# CONN_BOTT.net
KiCad netlist of a schematic drawn in Altium Designer
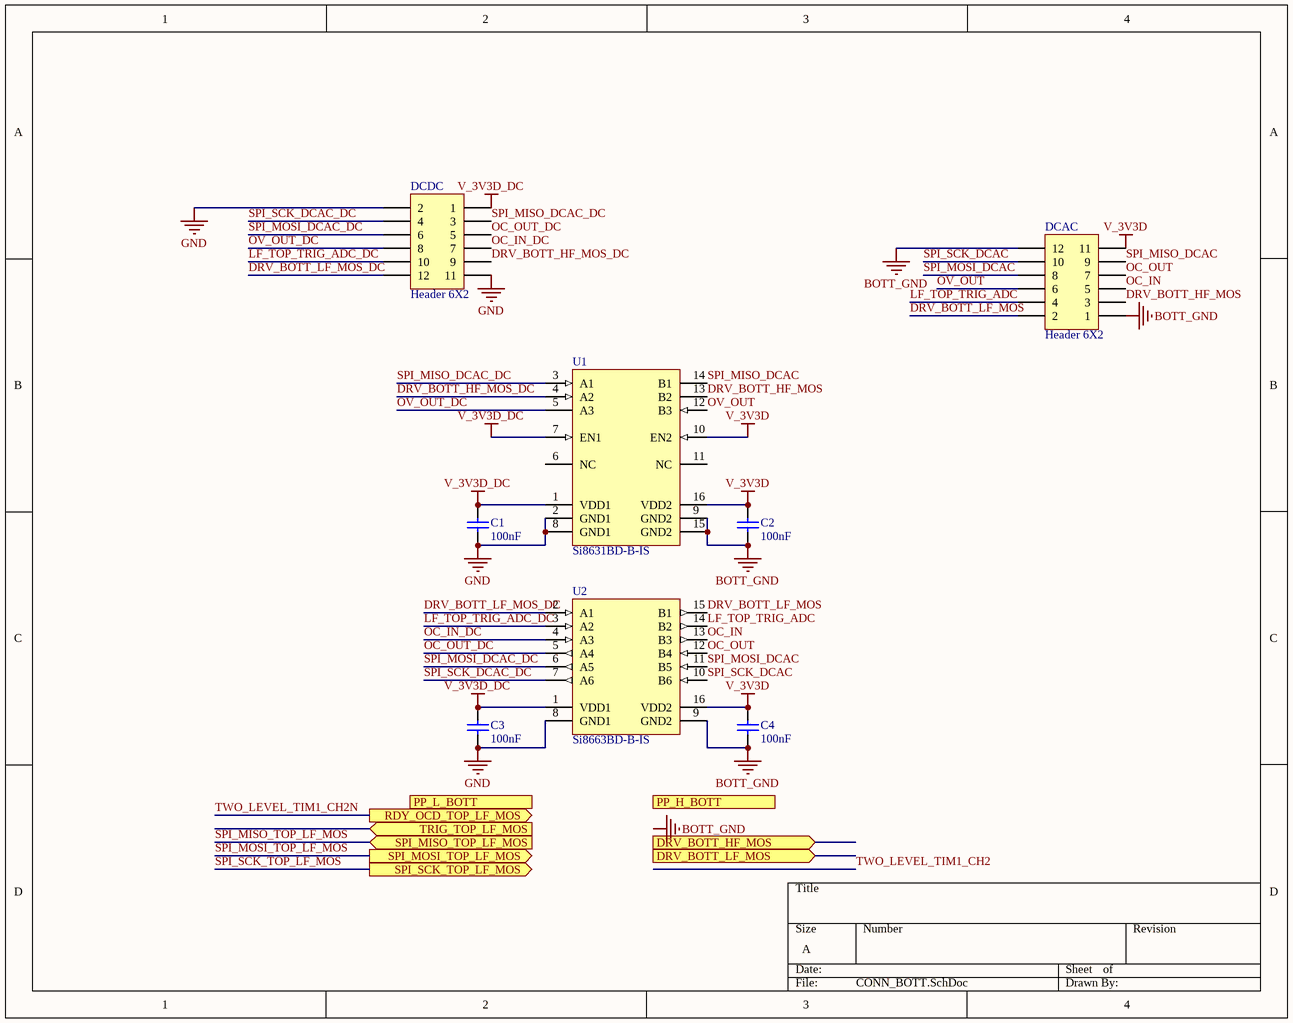
[diagram p0: CONN_BOTT.SchDoc]

(export (version "E")
  (design (tool "Eeschema 10.0.6"))
  (components
    (comp (ref "C1")
      (value "100nF")
      (footprint "SAMS-C0603-2_N")
      (description "Cap Ceramic 0.1uF 50VDC X7R 10% SMD 0603 Paper T/R")
      (fields
        (field (name "MANUFACTURER") "Samsung Electro-Mechanics")
        (field (name "MANUFACTURER PART NUMBER") "CL10B104KB8NNNC")
      )
      (libsource (lib "Altium Content Vault") (part "CAP-NP-2"))
    )
    (comp (ref "C2")
      (value "100nF")
      (footprint "SAMS-C0603-2_N")
      (description "Cap Ceramic 0.1uF 50VDC X7R 10% SMD 0603 Paper T/R")
      (fields
        (field (name "MANUFACTURER") "Samsung Electro-Mechanics")
        (field (name "MANUFACTURER PART NUMBER") "CL10B104KB8NNNC")
      )
      (libsource (lib "Altium Content Vault") (part "CAP-NP-2"))
    )
    (comp (ref "C3")
      (value "100nF")
      (footprint "SAMS-C0603-2_N")
      (description "Cap Ceramic 0.1uF 50VDC X7R 10% SMD 0603 Paper T/R")
      (fields
        (field (name "MANUFACTURER") "Samsung Electro-Mechanics")
        (field (name "MANUFACTURER PART NUMBER") "CL10B104KB8NNNC")
      )
      (libsource (lib "Altium Content Vault") (part "CAP-NP-2"))
    )
    (comp (ref "C4")
      (value "100nF")
      (footprint "SAMS-C0603-2_N")
      (description "Cap Ceramic 0.1uF 50VDC X7R 10% SMD 0603 Paper T/R")
      (fields
        (field (name "MANUFACTURER") "Samsung Electro-Mechanics")
        (field (name "MANUFACTURER PART NUMBER") "CL10B104KB8NNNC")
      )
      (libsource (lib "Altium Content Vault") (part "CAP-NP-2"))
    )
    (comp (ref "DCAC")
      (value "Header 6X2")
      (footprint "EDGE GOLDPIN 12P 1.27mm")
      (description "Header, 6-Pin, Dual row")
      (fields (field (name "PUBLISHER") "Altium Limited"))
      (libsource (lib "Miscellaneous Connectors") (part "Header 6X2"))
    )
    (comp (ref "DCDC")
      (value "Header 6X2")
      (footprint "EDGE GOLDPIN 12P 1.27mm")
      (description "Header, 6-Pin, Dual row")
      (fields (field (name "PUBLISHER") "Altium Limited"))
      (libsource (lib "") (part "Header 6X2_1"))
    )
    (comp (ref "U1")
      (value "Si8631BD-B-IS")
      (footprint "SLAB-SOIC-16-WB_N")
      (fields (field (name "MANUFACTURER") "Silicon Labs"))
      (libsource (lib "Altium Content Vault") (part "SLAB-Si8X31BB-SOIC-16-XB-16X"))
    )
    (comp (ref "U2")
      (value "Si8663BD-B-IS")
      (footprint "SLAB-SOIC-16-WB_N")
      (fields (field (name "MANUFACTURER") "Silicon Labs"))
      (libsource (lib "Altium Content Vault") (part "SLAB-Si8X63-SOIC-16"))
    )
  )
  (nets
    (net (code "1") (name "/DRV_BOTT_HF_MOS") (class "Default")
      (node (ref "DCAC") (pin "3") (pinfunction "3_3") (pintype "passive"))
      (node (ref "U1") (pin "13") (pinfunction "B2_13") (pintype "tri_state"))
    )
    (net (code "2") (name "/DRV_BOTT_HF_MOS_DC") (class "Default")
      (node (ref "DCDC") (pin "9") (pinfunction "9_9") (pintype "passive"))
      (node (ref "U1") (pin "4") (pinfunction "A2_4") (pintype "input"))
    )
    (net (code "3") (name "/DRV_BOTT_LF_MOS") (class "Default")
      (node (ref "DCAC") (pin "2") (pinfunction "2_2") (pintype "passive"))
      (node (ref "U2") (pin "15") (pinfunction "B1_15") (pintype "output"))
    )
    (net (code "4") (name "/DRV_BOTT_LF_MOS_DC") (class "Default")
      (node (ref "DCDC") (pin "12") (pinfunction "12_12") (pintype "passive"))
      (node (ref "U2") (pin "2") (pinfunction "A1_2") (pintype "input"))
    )
    (net (code "5") (name "/LF_TOP_TRIG_ADC") (class "Default")
      (node (ref "DCAC") (pin "4") (pinfunction "4_4") (pintype "passive"))
      (node (ref "U2") (pin "14") (pinfunction "B2_14") (pintype "output"))
    )
    (net (code "6") (name "/LF_TOP_TRIG_ADC_DC") (class "Default")
      (node (ref "DCDC") (pin "10") (pinfunction "10_10") (pintype "passive"))
      (node (ref "U2") (pin "3") (pinfunction "A2_3") (pintype "input"))
    )
    (net (code "7") (name "/OC_IN") (class "Default")
      (node (ref "DCAC") (pin "5") (pinfunction "5_5") (pintype "passive"))
      (node (ref "U2") (pin "13") (pinfunction "B3_13") (pintype "output"))
    )
    (net (code "8") (name "/OC_IN_DC") (class "Default")
      (node (ref "DCDC") (pin "7") (pinfunction "7_7") (pintype "passive"))
      (node (ref "U2") (pin "4") (pinfunction "A3_4") (pintype "input"))
    )
    (net (code "9") (name "/OC_OUT") (class "Default")
      (node (ref "DCAC") (pin "7") (pinfunction "7_7") (pintype "passive"))
      (node (ref "U2") (pin "12") (pinfunction "B4_12") (pintype "input"))
    )
    (net (code "10") (name "/OC_OUT_DC") (class "Default")
      (node (ref "DCDC") (pin "5") (pinfunction "5_5") (pintype "passive"))
      (node (ref "U2") (pin "5") (pinfunction "A4_5") (pintype "output"))
    )
    (net (code "11") (name "/OV_OUT") (class "Default")
      (node (ref "DCAC") (pin "6") (pinfunction "6_6") (pintype "passive"))
      (node (ref "U1") (pin "12") (pinfunction "B3_12") (pintype "input"))
    )
    (net (code "12") (name "/OV_OUT_DC") (class "Default")
      (node (ref "DCDC") (pin "8") (pinfunction "8_8") (pintype "passive"))
      (node (ref "U1") (pin "5") (pinfunction "A3_5") (pintype "tri_state"))
    )
    (net (code "15") (name "/SPI_MISO_DCAC") (class "Default")
      (node (ref "DCAC") (pin "9") (pinfunction "9_9") (pintype "passive"))
      (node (ref "U1") (pin "14") (pinfunction "B1_14") (pintype "tri_state"))
    )
    (net (code "16") (name "/SPI_MISO_DCAC_DC") (class "Default")
      (node (ref "DCDC") (pin "3") (pinfunction "3_3") (pintype "passive"))
      (node (ref "U1") (pin "3") (pinfunction "A1_3") (pintype "input"))
    )
    (net (code "18") (name "/SPI_MOSI_DCAC") (class "Default")
      (node (ref "DCAC") (pin "8") (pinfunction "8_8") (pintype "passive"))
      (node (ref "U2") (pin "11") (pinfunction "B5_11") (pintype "input"))
    )
    (net (code "19") (name "/SPI_MOSI_DCAC_DC") (class "Default")
      (node (ref "DCDC") (pin "6") (pinfunction "6_6") (pintype "passive"))
      (node (ref "U2") (pin "6") (pinfunction "A5_6") (pintype "output"))
    )
    (net (code "21") (name "/SPI_SCK_DCAC") (class "Default")
      (node (ref "DCAC") (pin "10") (pinfunction "10_10") (pintype "passive"))
      (node (ref "U2") (pin "10") (pinfunction "B6_10") (pintype "input"))
    )
    (net (code "22") (name "/SPI_SCK_DCAC_DC") (class "Default")
      (node (ref "DCDC") (pin "4") (pinfunction "4_4") (pintype "passive"))
      (node (ref "U2") (pin "7") (pinfunction "A6_7") (pintype "output"))
    )
    (net (code "27") (name "BOTT_GND") (class "Default")
      (node (ref "C2") (pin "2") (pinfunction "2_2") (pintype "passive"))
      (node (ref "C4") (pin "2") (pinfunction "2_2") (pintype "passive"))
      (node (ref "DCAC") (pin "1") (pinfunction "1_1") (pintype "passive"))
      (node (ref "DCAC") (pin "12") (pinfunction "12_12") (pintype "passive"))
      (node (ref "U1") (pin "15") (pinfunction "GND2_15") (pintype "power_in"))
      (node (ref "U1") (pin "9") (pinfunction "GND2_9") (pintype "power_in"))
      (node (ref "U2") (pin "9") (pinfunction "GND2_9") (pintype "power_in"))
    )
    (net (code "28") (name "GND") (class "Default")
      (node (ref "C1") (pin "2") (pinfunction "2_2") (pintype "passive"))
      (node (ref "C3") (pin "2") (pinfunction "2_2") (pintype "passive"))
      (node (ref "DCDC") (pin "11") (pinfunction "11_11") (pintype "passive"))
      (node (ref "DCDC") (pin "2") (pinfunction "2_2") (pintype "passive"))
      (node (ref "U1") (pin "2") (pinfunction "GND1_2") (pintype "power_in"))
      (node (ref "U1") (pin "8") (pinfunction "GND1_8") (pintype "power_in"))
      (node (ref "U2") (pin "8") (pinfunction "GND1_8") (pintype "power_in"))
    )
    (net (code "29") (name "V_3V3D") (class "Default")
      (node (ref "C2") (pin "1") (pinfunction "1_1") (pintype "passive"))
      (node (ref "C4") (pin "1") (pinfunction "1_1") (pintype "passive"))
      (node (ref "DCAC") (pin "11") (pinfunction "11_11") (pintype "passive"))
      (node (ref "U1") (pin "10") (pinfunction "EN2_10") (pintype "input"))
      (node (ref "U1") (pin "16") (pinfunction "VDD2_16") (pintype "power_in"))
      (node (ref "U2") (pin "16") (pinfunction "VDD2_16") (pintype "power_in"))
    )
    (net (code "30") (name "V_3V3D_DC") (class "Default")
      (node (ref "C1") (pin "1") (pinfunction "1_1") (pintype "passive"))
      (node (ref "C3") (pin "1") (pinfunction "1_1") (pintype "passive"))
      (node (ref "DCDC") (pin "1") (pinfunction "1_1") (pintype "passive"))
      (node (ref "U1") (pin "1") (pinfunction "VDD1_1") (pintype "power_in"))
      (node (ref "U1") (pin "7") (pinfunction "EN1_7") (pintype "input"))
      (node (ref "U2") (pin "1") (pinfunction "VDD1_1") (pintype "power_in"))
    )
    (net (code "31") (name "unconnected-(U1-NC-Pad6)") (class "Default")
      (node (ref "U1") (pin "6") (pinfunction "NC_6") (pintype "passive"))
    )
    (net (code "32") (name "unconnected-(U1-NC-Pad11)") (class "Default")
      (node (ref "U1") (pin "11") (pinfunction "NC_11") (pintype "passive"))
    )
  )
)
